# RS485_Under_Leaf_Sensor_Socket.net
KiCad netlist of a schematic drawn in Altium Designer
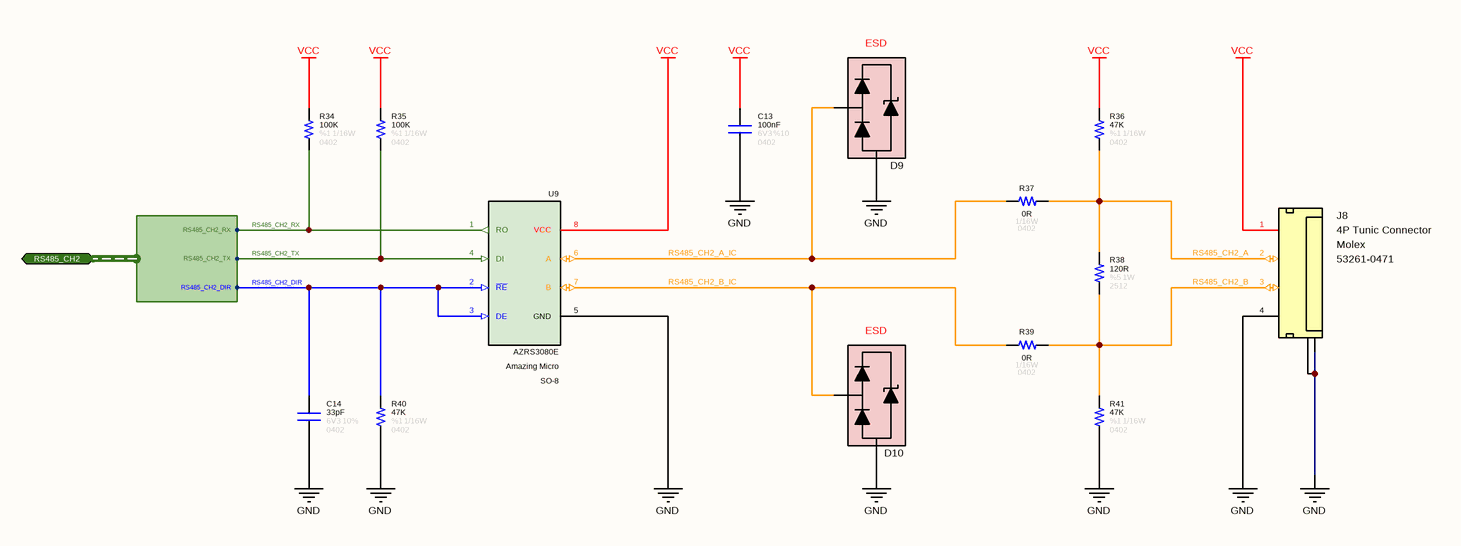
[diagram p0: RS485 Under Leaf Sensor Socket.SchDoc]

(export (version "E")
  (design (tool "Eeschema 10.0.6"))
  (components
    (comp (ref "C13")
      (value "100nF")
      (footprint "CAPACITOR_0402")
      (description "Capacitor - 100nF [0402-6V3] (Ceramic)")
      (fields
        (field (name "MANUFACTURER PART NUMBER") "04026D104KAT4A")
        (field (name "TOLERANCE") "%10")
        (field (name "VOLTAGE") "6V3")
        (field (name "CASE") "0402")
        (field (name "Comment") "Capacitor - 100nF [0402] (Ceramic)")
      )
      (libsource (lib "P101DA_Library") (part "Capacitor - 100nF [0402-6V3]"))
    )
    (comp (ref "C14")
      (value "33pF")
      (footprint "CAPACITOR_0402")
      (description "Capacitor - 33pF [0402] (Ceramic)")
      (fields
        (field (name "MANUFACTURER PART NUMBER") "C0402C330J9RACAUTO")
        (field (name "TOLERANCE") "10%")
        (field (name "CASE") "0402")
        (field (name "VOLTAGE") "6V3")
      )
      (libsource (lib "P101DA_Library") (part "Capacitor - 33pF [0402-6V3]"))
    )
    (comp (ref "D9")
      (value "0402ESDA-MLP1")
      (footprint "ESD_0402")
      (description "SUPPRESSOR ESD 30VDC 0402 HFREE")
      (libsource (lib "P101DA_Library") (part "Diode - TPD1E05U06DPYR"))
    )
    (comp (ref "D10")
      (value "0402ESDA-MLP1")
      (footprint "ESD_0402")
      (description "SUPPRESSOR ESD 30VDC 0402 HFREE")
      (libsource (lib "P101DA_Library") (part "Diode - TPD1E05U06DPYR"))
    )
    (comp (ref "J8")
      (value "4P SMD Tunic Connector")
      (footprint "Connector_Tunic 4P")
      (description "Mini Tunic Connector with 4P")
      (fields
        (field (name "MANUFACTURER NAME") "Molex")
        (field (name "MANUFACTURER PART NUMBER") "53261-0471")
      )
      (libsource (lib "P101DA_Library") (part "Connector - Mini Tunic 4P (1.25)"))
    )
    (comp (ref "R34")
      (value "100K")
      (footprint "RESISTOR_0402")
      (description "Thick Film Resistors - SMD 1/16 W 100 KOhm 1%")
      (fields
        (field (name "MANUFACTURER PART NUMBER") "CRCW0402100KFKED")
        (field (name "TOLERANCE") "%1")
        (field (name "CASE") "0402")
        (field (name "POWER") "1/16W")
        (field (name "Comment") "100K - 0402 - %1 - 1/16W")
      )
      (libsource (lib "P101DA_Library") (part "Resistor - 100K [0402]"))
    )
    (comp (ref "R35")
      (value "100K")
      (footprint "RESISTOR_0402")
      (description "Thick Film Resistors - SMD 1/16 W 100 KOhm 1%")
      (fields
        (field (name "MANUFACTURER PART NUMBER") "CRCW0402100KFKED")
        (field (name "TOLERANCE") "%1")
        (field (name "CASE") "0402")
        (field (name "POWER") "1/16W")
        (field (name "Comment") "100K - 0402 - %1 - 1/16W")
      )
      (libsource (lib "P101DA_Library") (part "Resistor - 100K [0402]"))
    )
    (comp (ref "R36")
      (value "47K")
      (footprint "RESISTOR_0402")
      (description "Thick Film Resistors - SMD 1/16 W 47 KOhm 1%")
      (fields
        (field (name "MANUFACTURER PART NUMBER") "CRCW040247K0FKED")
        (field (name "TOLERANCE") "%1")
        (field (name "CASE") "0402")
        (field (name "POWER") "1/16W")
        (field (name "Comment") "47K - 0402 - %1 - 1/16W")
      )
      (libsource (lib "P101DA_Library") (part "Resistor - 47K [0402]"))
    )
    (comp (ref "R37")
      (value "0R")
      (footprint "RESISTOR_0402")
      (description "Thick Film Resistors - SMD 1/16 W 0 Ohm")
      (fields
        (field (name "MANUFACTURER PART NUMBER") "CRCW04020000Z0ED")
        (field (name "CASE") "0402")
        (field (name "POWER") "1/16W")
        (field (name "Comment") "0R - 0402 - %1 - 1/16W")
      )
      (libsource (lib "P101DA_Library") (part "Resistor - 0R [0402]"))
    )
    (comp (ref "R38")
      (value "120R")
      (footprint "RESISTOR_2512")
      (description "Thick Film Resistors - SMD 1 W 120 Ohm 5%")
      (fields
        (field (name "MANUFACTURER PART NUMBER") "RC2512JK-07120RL")
        (field (name "TOLERANCE") "%5")
        (field (name "CASE") "2512")
        (field (name "POWER") "1W")
        (field (name "Comment") "120R - 2512 - %5 - 1W")
      )
      (libsource (lib "P101DA_Library") (part "Resistor - 120R [2512]"))
    )
    (comp (ref "R39")
      (value "0R")
      (footprint "RESISTOR_0402")
      (description "Thick Film Resistors - SMD 1/16 W 0 Ohm")
      (fields
        (field (name "MANUFACTURER PART NUMBER") "CRCW04020000Z0ED")
        (field (name "CASE") "0402")
        (field (name "POWER") "1/16W")
        (field (name "Comment") "0R - 0402 - %1 - 1/16W")
      )
      (libsource (lib "P101DA_Library") (part "Resistor - 0R [0402]"))
    )
    (comp (ref "R40")
      (value "47K")
      (footprint "RESISTOR_0402")
      (description "Thick Film Resistors - SMD 1/16 W 47 KOhm 1%")
      (fields
        (field (name "MANUFACTURER PART NUMBER") "CRCW040247K0FKED")
        (field (name "TOLERANCE") "%1")
        (field (name "CASE") "0402")
        (field (name "POWER") "1/16W")
        (field (name "Comment") "47K - 0402 - %1 - 1/16W")
      )
      (libsource (lib "P101DA_Library") (part "Resistor - 47K [0402]"))
    )
    (comp (ref "R41")
      (value "47K")
      (footprint "RESISTOR_0402")
      (description "Thick Film Resistors - SMD 1/16 W 47 KOhm 1%")
      (fields
        (field (name "MANUFACTURER PART NUMBER") "CRCW040247K0FKED")
        (field (name "TOLERANCE") "%1")
        (field (name "CASE") "0402")
        (field (name "POWER") "1/16W")
        (field (name "Comment") "47K - 0402 - %1 - 1/16W")
      )
      (libsource (lib "P101DA_Library") (part "Resistor - 47K [0402]"))
    )
    (comp (ref "U9")
      (value "RS485 Modulator")
      (footprint "SOP-8L (AZRS3080E)")
      (description "Half-duplex RS485 transceiver.")
      (fields
        (field (name "CASE") "SO-8")
        (field (name "MANUFACTURER PART NUMBER") "AZRS3080E")
        (field (name "MANUFACTURER NAME") "Amazing Micro")
      )
      (libsource (lib "P101DA_Library") (part "IC - AZRS3080E"))
    )
  )
  (nets
    (net (code "2") (name "/RS485_CH2_A") (class "Default")
      (node (ref "J8") (pin "2") (pinfunction "Pin-2_2") (pintype "bidirectional"))
      (node (ref "R36") (pin "1") (pinfunction "1_1") (pintype "passive"))
      (node (ref "R37") (pin "1") (pinfunction "1_1") (pintype "passive"))
      (node (ref "R38") (pin "2") (pinfunction "2_2") (pintype "passive"))
    )
    (net (code "3") (name "/RS485_CH2_A_IC") (class "Default")
      (node (ref "D9") (pin "1") (pinfunction "I/O_1") (pintype "passive"))
      (node (ref "R37") (pin "2") (pinfunction "2_2") (pintype "passive"))
      (node (ref "U9") (pin "6") (pinfunction "A_6") (pintype "bidirectional"))
    )
    (net (code "4") (name "/RS485_CH2_B") (class "Default")
      (node (ref "J8") (pin "3") (pinfunction "Pin-3_3") (pintype "bidirectional"))
      (node (ref "R38") (pin "1") (pinfunction "1_1") (pintype "passive"))
      (node (ref "R39") (pin "1") (pinfunction "1_1") (pintype "passive"))
      (node (ref "R41") (pin "2") (pinfunction "2_2") (pintype "passive"))
    )
    (net (code "5") (name "/RS485_CH2_B_IC") (class "Default")
      (node (ref "D10") (pin "1") (pinfunction "I/O_1") (pintype "passive"))
      (node (ref "R39") (pin "2") (pinfunction "2_2") (pintype "passive"))
      (node (ref "U9") (pin "7") (pinfunction "B_7") (pintype "bidirectional"))
    )
    (net (code "6") (name "/RS485_CH2_DIR") (class "Default")
      (node (ref "C14") (pin "2") (pinfunction "2_2") (pintype "passive"))
      (node (ref "R40") (pin "2") (pinfunction "2_2") (pintype "passive"))
      (node (ref "U9") (pin "2") (pinfunction "~{RE}_2") (pintype "input"))
      (node (ref "U9") (pin "3") (pinfunction "DE_3") (pintype "input"))
    )
    (net (code "7") (name "/RS485_CH2_RX") (class "Default")
      (node (ref "R34") (pin "1") (pinfunction "1_1") (pintype "passive"))
      (node (ref "U9") (pin "1") (pinfunction "RO_1") (pintype "output"))
    )
    (net (code "8") (name "/RS485_CH2_TX") (class "Default")
      (node (ref "R35") (pin "1") (pinfunction "1_1") (pintype "passive"))
      (node (ref "U9") (pin "4") (pinfunction "DI_4") (pintype "input"))
    )
    (net (code "10") (name "GND") (class "Default")
      (node (ref "C13") (pin "1") (pinfunction "1_1") (pintype "passive"))
      (node (ref "C14") (pin "1") (pinfunction "1_1") (pintype "passive"))
      (node (ref "D10") (pin "2") (pinfunction "GND_2") (pintype "passive"))
      (node (ref "D9") (pin "2") (pinfunction "GND_2") (pintype "passive"))
      (node (ref "J8") (pin "4") (pinfunction "Pin-4_4") (pintype "power_in"))
      (node (ref "J8") (pin "5") (pinfunction "GND_5") (pintype "passive"))
      (node (ref "J8") (pin "6") (pinfunction "GND_6") (pintype "passive"))
      (node (ref "R40") (pin "1") (pinfunction "1_1") (pintype "passive"))
      (node (ref "R41") (pin "1") (pinfunction "1_1") (pintype "passive"))
      (node (ref "U9") (pin "5") (pinfunction "GND_5") (pintype "passive"))
    )
    (net (code "11") (name "VCC") (class "Default")
      (node (ref "C13") (pin "2") (pinfunction "2_2") (pintype "passive"))
      (node (ref "J8") (pin "1") (pinfunction "Pin-1_1") (pintype "power_in"))
      (node (ref "R34") (pin "2") (pinfunction "2_2") (pintype "passive"))
      (node (ref "R35") (pin "2") (pinfunction "2_2") (pintype "passive"))
      (node (ref "R36") (pin "2") (pinfunction "2_2") (pintype "passive"))
      (node (ref "U9") (pin "8") (pinfunction "VCC_8") (pintype "power_in"))
    )
  )
)
